# sc_v1.net
KiCad netlist of a schematic drawn in EAGLE
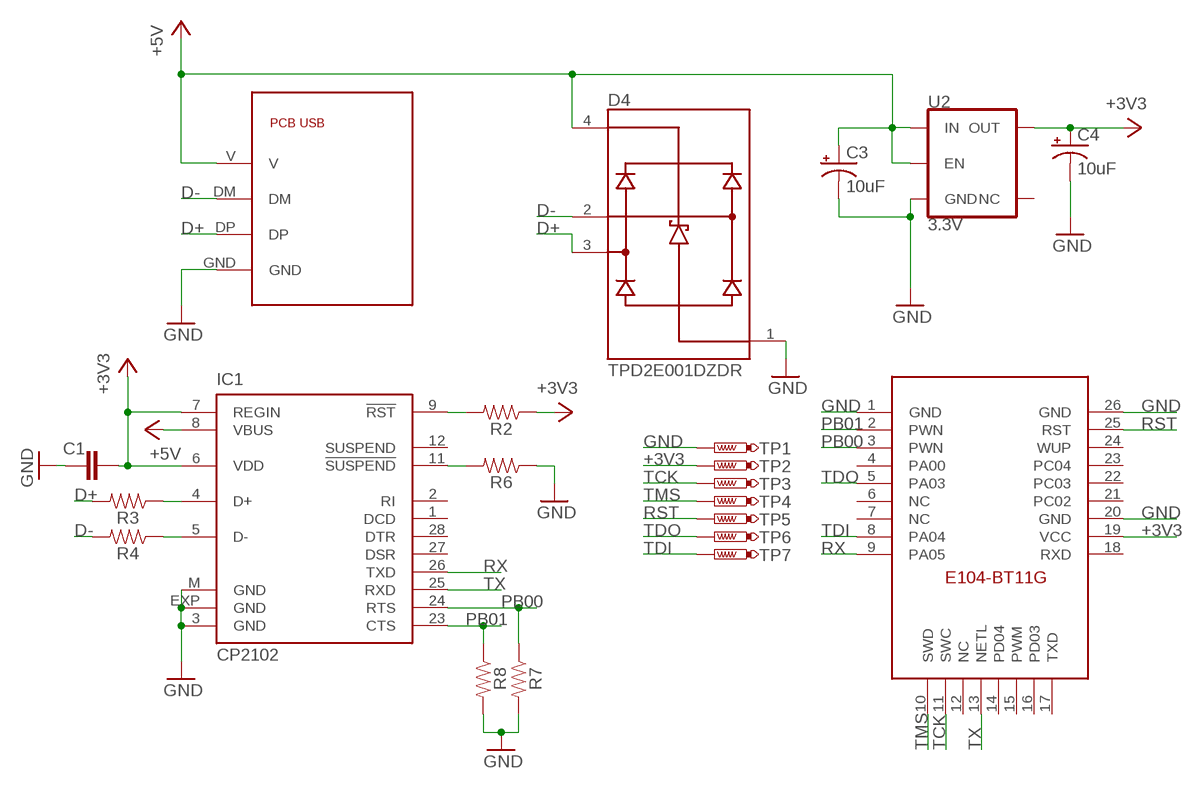
[diagram p0: schematic, sheet 1]

(export (version "E")
  (design (tool "Eeschema 10.0.6"))
  (components
    (comp (ref "C1")
      (value "100nf")
      (footprint "eagle-import:CAPC1005X40N")
      (fields (field (name "MF") "Yageo") (field (name "MP") "RC0402FR-073M6L"))
      (libsource (lib "eagle-import") (part "CAP0402"))
    )
    (comp (ref "C3")
      (value "10uF")
      (footprint "eagle-import:0603-POLAR")
      (libsource (lib "eagle-import") (part "10UF-POLAR-0603-6.3V-20%(TANT)"))
    )
    (comp (ref "C4")
      (value "10uF")
      (footprint "eagle-import:0603-POLAR")
      (libsource (lib "eagle-import") (part "10UF-POLAR-0603-6.3V-20%(TANT)"))
    )
    (comp (ref "D4")
      (value "TPD2E001DZDR")
      (footprint "eagle-import:SOT192P237X122-4N")
      (fields (field (name "MF") "Texas Instruments"))
      (libsource (lib "eagle-import") (part "TPD2E001DZDR"))
    )
    (comp (ref "IC1")
      (value "CP2102")
      (footprint "eagle-import:MLP28")
      (fields (field (name "MF") "FARNELL") (field (name "MPN") "CP2102-GM"))
      (libsource (lib "eagle-import") (part "CP2102"))
    )
    (comp (ref "R2")
      (value "4.7k")
      (footprint "eagle-import:0402")
      (libsource (lib "eagle-import") (part "RESISTOR0402"))
    )
    (comp (ref "R3")
      (value "30Ohm")
      (footprint "eagle-import:0402")
      (libsource (lib "eagle-import") (part "RESISTOR0402"))
    )
    (comp (ref "R4")
      (value "30Ohm")
      (footprint "eagle-import:0402")
      (libsource (lib "eagle-import") (part "RESISTOR0402"))
    )
    (comp (ref "R6")
      (value "10k")
      (footprint "eagle-import:0402")
      (libsource (lib "eagle-import") (part "RESISTOR0402"))
    )
    (comp (ref "R7")
      (value "10k")
      (footprint "eagle-import:0402")
      (libsource (lib "eagle-import") (part "RESISTOR0402"))
    )
    (comp (ref "R8")
      (value "10k")
      (footprint "eagle-import:0402")
      (libsource (lib "eagle-import") (part "RESISTOR0402"))
    )
    (comp (ref "TP1")
      (value "PTR1TP10R")
      (footprint "eagle-import:TP10R")
      (libsource (lib "eagle-import") (part "PTR1TP10R"))
    )
    (comp (ref "TP2")
      (value "PTR1TP10R")
      (footprint "eagle-import:TP10R")
      (libsource (lib "eagle-import") (part "PTR1TP10R"))
    )
    (comp (ref "TP3")
      (value "PTR1TP10R")
      (footprint "eagle-import:TP10R")
      (libsource (lib "eagle-import") (part "PTR1TP10R"))
    )
    (comp (ref "TP4")
      (value "PTR1TP10R")
      (footprint "eagle-import:TP10R")
      (libsource (lib "eagle-import") (part "PTR1TP10R"))
    )
    (comp (ref "TP5")
      (value "PTR1TP10R")
      (footprint "eagle-import:TP10R")
      (libsource (lib "eagle-import") (part "PTR1TP10R"))
    )
    (comp (ref "TP6")
      (value "PTR1TP10R")
      (footprint "eagle-import:TP10R")
      (libsource (lib "eagle-import") (part "PTR1TP10R"))
    )
    (comp (ref "TP7")
      (value "PTR1TP10R")
      (footprint "eagle-import:TP10R")
      (libsource (lib "eagle-import") (part "PTR1TP10R"))
    )
    (comp (ref "U$1")
      (value "E104-BT11G-PCBPCB")
      (footprint "eagle-import:E104-BT11G-PCB")
      (libsource (lib "eagle-import") (part "E104-BT11G-PCBPCB"))
    )
    (comp (ref "U$2")
      (value "PCB_USBNOBACK")
      (footprint "eagle-import:PCB_USB")
      (libsource (lib "eagle-import") (part "PCB_USBNOBACK"))
    )
    (comp (ref "U2")
      (value "3.3V")
      (footprint "eagle-import:SOT23-5")
      (libsource (lib "eagle-import") (part "V_REG_AP2112K-3.3V"))
    )
  )
  (nets
    (net (code "1") (name "+3V3") (class "Default")
      (node (ref "C1") (pin "2") (pinfunction "2_2") (pintype "passive"))
      (node (ref "C4") (pin "+") (pinfunction "+_+") (pintype "passive"))
      (node (ref "IC1") (pin "6") (pinfunction "VDD_6") (pintype "power_in"))
      (node (ref "IC1") (pin "7") (pinfunction "REGIN_7") (pintype "passive"))
      (node (ref "R2") (pin "1") (pinfunction "1_1") (pintype "passive"))
      (node (ref "TP2") (pin "TP") (pinfunction "TP_TP") (pintype "input"))
      (node (ref "U$1") (pin "19") (pinfunction "VCC_19") (pintype "bidirectional"))
      (node (ref "U2") (pin "5") (pinfunction "OUT_5") (pintype "passive"))
    )
    (net (code "2") (name "+5V") (class "Default")
      (node (ref "C3") (pin "+") (pinfunction "+_+") (pintype "passive"))
      (node (ref "D4") (pin "4") (pinfunction "VCC_4") (pintype "power_in"))
      (node (ref "IC1") (pin "8") (pinfunction "VBUS_8") (pintype "input"))
      (node (ref "U$2") (pin "V") (pinfunction "V_V") (pintype "bidirectional"))
      (node (ref "U2") (pin "1") (pinfunction "IN_1") (pintype "input"))
      (node (ref "U2") (pin "3") (pinfunction "EN_3") (pintype "input"))
    )
    (net (code "3") (name "/D+") (class "Default")
      (node (ref "D4") (pin "3") (pinfunction "IO2_3") (pintype "bidirectional"))
      (node (ref "R3") (pin "2") (pinfunction "2_2") (pintype "passive"))
      (node (ref "U$2") (pin "DP") (pinfunction "DP_DP") (pintype "bidirectional"))
    )
    (net (code "4") (name "/D-") (class "Default")
      (node (ref "D4") (pin "2") (pinfunction "IO1_2") (pintype "bidirectional"))
      (node (ref "R4") (pin "2") (pinfunction "2_2") (pintype "passive"))
      (node (ref "U$2") (pin "DM") (pinfunction "DM_DM") (pintype "bidirectional"))
    )
    (net (code "5") (name "/PB00") (class "Default")
      (node (ref "IC1") (pin "24") (pinfunction "RTS_24") (pintype "output"))
      (node (ref "R7") (pin "1") (pinfunction "1_1") (pintype "passive"))
      (node (ref "U$1") (pin "3") (pinfunction "PWN_3") (pintype "bidirectional"))
    )
    (net (code "6") (name "/PB01") (class "Default")
      (node (ref "IC1") (pin "23") (pinfunction "CTS_23") (pintype "input"))
      (node (ref "R8") (pin "1") (pinfunction "1_1") (pintype "passive"))
      (node (ref "U$1") (pin "2") (pinfunction "PWN_2") (pintype "bidirectional"))
    )
    (net (code "7") (name "/RST") (class "Default")
      (node (ref "TP5") (pin "TP") (pinfunction "TP_TP") (pintype "input"))
      (node (ref "U$1") (pin "25") (pinfunction "RST_25") (pintype "bidirectional"))
    )
    (net (code "8") (name "/RX") (class "Default")
      (node (ref "IC1") (pin "26") (pinfunction "TXD_26") (pintype "output"))
      (node (ref "U$1") (pin "9") (pinfunction "PA05_9") (pintype "bidirectional"))
    )
    (net (code "9") (name "/TCK") (class "Default")
      (node (ref "TP3") (pin "TP") (pinfunction "TP_TP") (pintype "input"))
      (node (ref "U$1") (pin "11") (pinfunction "SWC_11") (pintype "bidirectional"))
    )
    (net (code "10") (name "/TDI") (class "Default")
      (node (ref "TP7") (pin "TP") (pinfunction "TP_TP") (pintype "input"))
      (node (ref "U$1") (pin "8") (pinfunction "PA04_8") (pintype "bidirectional"))
    )
    (net (code "11") (name "/TDO") (class "Default")
      (node (ref "TP6") (pin "TP") (pinfunction "TP_TP") (pintype "input"))
      (node (ref "U$1") (pin "5") (pinfunction "PA03_5") (pintype "bidirectional"))
    )
    (net (code "12") (name "/TMS") (class "Default")
      (node (ref "TP4") (pin "TP") (pinfunction "TP_TP") (pintype "input"))
      (node (ref "U$1") (pin "10") (pinfunction "SWD_10") (pintype "bidirectional"))
    )
    (net (code "13") (name "/TX") (class "Default")
      (node (ref "IC1") (pin "25") (pinfunction "RXD_25") (pintype "input"))
      (node (ref "U$1") (pin "13") (pinfunction "NETL_13") (pintype "bidirectional"))
    )
    (net (code "14") (name "GND") (class "Default")
      (node (ref "C1") (pin "1") (pinfunction "1_1") (pintype "passive"))
      (node (ref "C3") (pin "-") (pinfunction "-_-") (pintype "passive"))
      (node (ref "C4") (pin "-") (pinfunction "-_-") (pintype "passive"))
      (node (ref "D4") (pin "1") (pinfunction "GND_1") (pintype "power_in"))
      (node (ref "IC1") (pin "3") (pinfunction "GND_3") (pintype "power_in"))
      (node (ref "IC1") (pin "EXP") (pinfunction "GND_EXP") (pintype "power_in"))
      (node (ref "IC1") (pin "M") (pinfunction "GND_M") (pintype "power_in"))
      (node (ref "R6") (pin "1") (pinfunction "1_1") (pintype "passive"))
      (node (ref "R7") (pin "2") (pinfunction "2_2") (pintype "passive"))
      (node (ref "R8") (pin "2") (pinfunction "2_2") (pintype "passive"))
      (node (ref "TP1") (pin "TP") (pinfunction "TP_TP") (pintype "input"))
      (node (ref "U$1") (pin "1") (pinfunction "GND_1") (pintype "bidirectional"))
      (node (ref "U$1") (pin "20") (pinfunction "GND_20") (pintype "bidirectional"))
      (node (ref "U$1") (pin "26") (pinfunction "GND_26") (pintype "bidirectional"))
      (node (ref "U$2") (pin "GND") (pinfunction "GND_GND") (pintype "bidirectional"))
      (node (ref "U2") (pin "2") (pinfunction "GND_2") (pintype "input"))
    )
    (net (code "15") (name "Net-(IC1-D+)") (class "Default")
      (node (ref "IC1") (pin "4") (pinfunction "D+_4") (pintype "bidirectional"))
      (node (ref "R3") (pin "1") (pinfunction "1_1") (pintype "passive"))
    )
    (net (code "16") (name "Net-(IC1-D-)") (class "Default")
      (node (ref "IC1") (pin "5") (pinfunction "D-_5") (pintype "bidirectional"))
      (node (ref "R4") (pin "1") (pinfunction "1_1") (pintype "passive"))
    )
    (net (code "17") (name "Net-(IC1-~{RST})") (class "Default")
      (node (ref "IC1") (pin "9") (pinfunction "~{RST}_9") (pintype "bidirectional"))
      (node (ref "R2") (pin "2") (pinfunction "2_2") (pintype "passive"))
    )
    (net (code "18") (name "Net-(IC1-~{SUSPEND})") (class "Default")
      (node (ref "IC1") (pin "11") (pinfunction "~{SUSPEND}_11") (pintype "output"))
      (node (ref "R6") (pin "2") (pinfunction "2_2") (pintype "passive"))
    )
    (net (code "19") (name "unconnected-(IC1-DCD-Pad1)") (class "Default")
      (node (ref "IC1") (pin "1") (pinfunction "DCD_1") (pintype "input"))
    )
    (net (code "20") (name "unconnected-(IC1-DSR-Pad27)") (class "Default")
      (node (ref "IC1") (pin "27") (pinfunction "DSR_27") (pintype "input"))
    )
    (net (code "21") (name "unconnected-(IC1-DTR-Pad28)") (class "Default")
      (node (ref "IC1") (pin "28") (pinfunction "DTR_28") (pintype "output"))
    )
    (net (code "22") (name "unconnected-(IC1-RI-Pad2)") (class "Default")
      (node (ref "IC1") (pin "2") (pinfunction "RI_2") (pintype "input"))
    )
    (net (code "23") (name "unconnected-(IC1-SUSPEND-Pad12)") (class "Default")
      (node (ref "IC1") (pin "12") (pinfunction "SUSPEND_12") (pintype "output"))
    )
    (net (code "24") (name "unconnected-(U$1-NC-Pad6)") (class "Default")
      (node (ref "U$1") (pin "6") (pinfunction "NC_6") (pintype "bidirectional"))
    )
    (net (code "25") (name "unconnected-(U$1-NC-Pad7)") (class "Default")
      (node (ref "U$1") (pin "7") (pinfunction "NC_7") (pintype "bidirectional"))
    )
    (net (code "26") (name "unconnected-(U$1-NC-Pad12)") (class "Default")
      (node (ref "U$1") (pin "12") (pinfunction "NC_12") (pintype "bidirectional"))
    )
    (net (code "27") (name "unconnected-(U$1-PA00-Pad4)") (class "Default")
      (node (ref "U$1") (pin "4") (pinfunction "PA00_4") (pintype "bidirectional"))
    )
    (net (code "28") (name "unconnected-(U$1-PC02-Pad21)") (class "Default")
      (node (ref "U$1") (pin "21") (pinfunction "PC02_21") (pintype "bidirectional"))
    )
    (net (code "29") (name "unconnected-(U$1-PC03-Pad22)") (class "Default")
      (node (ref "U$1") (pin "22") (pinfunction "PC03_22") (pintype "bidirectional"))
    )
    (net (code "30") (name "unconnected-(U$1-PC04-Pad23)") (class "Default")
      (node (ref "U$1") (pin "23") (pinfunction "PC04_23") (pintype "bidirectional"))
    )
    (net (code "31") (name "unconnected-(U$1-PD03-Pad16)") (class "Default")
      (node (ref "U$1") (pin "16") (pinfunction "PD03_16") (pintype "bidirectional"))
    )
    (net (code "32") (name "unconnected-(U$1-PD04-Pad14)") (class "Default")
      (node (ref "U$1") (pin "14") (pinfunction "PD04_14") (pintype "bidirectional"))
    )
    (net (code "33") (name "unconnected-(U$1-PWM-Pad15)") (class "Default")
      (node (ref "U$1") (pin "15") (pinfunction "PWM_15") (pintype "bidirectional"))
    )
    (net (code "34") (name "unconnected-(U$1-RXD-Pad18)") (class "Default")
      (node (ref "U$1") (pin "18") (pinfunction "RXD_18") (pintype "bidirectional"))
    )
    (net (code "35") (name "unconnected-(U$1-TXD-Pad17)") (class "Default")
      (node (ref "U$1") (pin "17") (pinfunction "TXD_17") (pintype "bidirectional"))
    )
    (net (code "36") (name "unconnected-(U$1-WUP-Pad24)") (class "Default")
      (node (ref "U$1") (pin "24") (pinfunction "WUP_24") (pintype "bidirectional"))
    )
    (net (code "37") (name "unconnected-(U2-NC-Pad4)") (class "Default")
      (node (ref "U2") (pin "4") (pinfunction "NC_4") (pintype "no_connect"))
    )
  )
)
